# alpha85_mem_acia_pio-routed.net
KiCad netlist of a schematic drawn in EAGLE
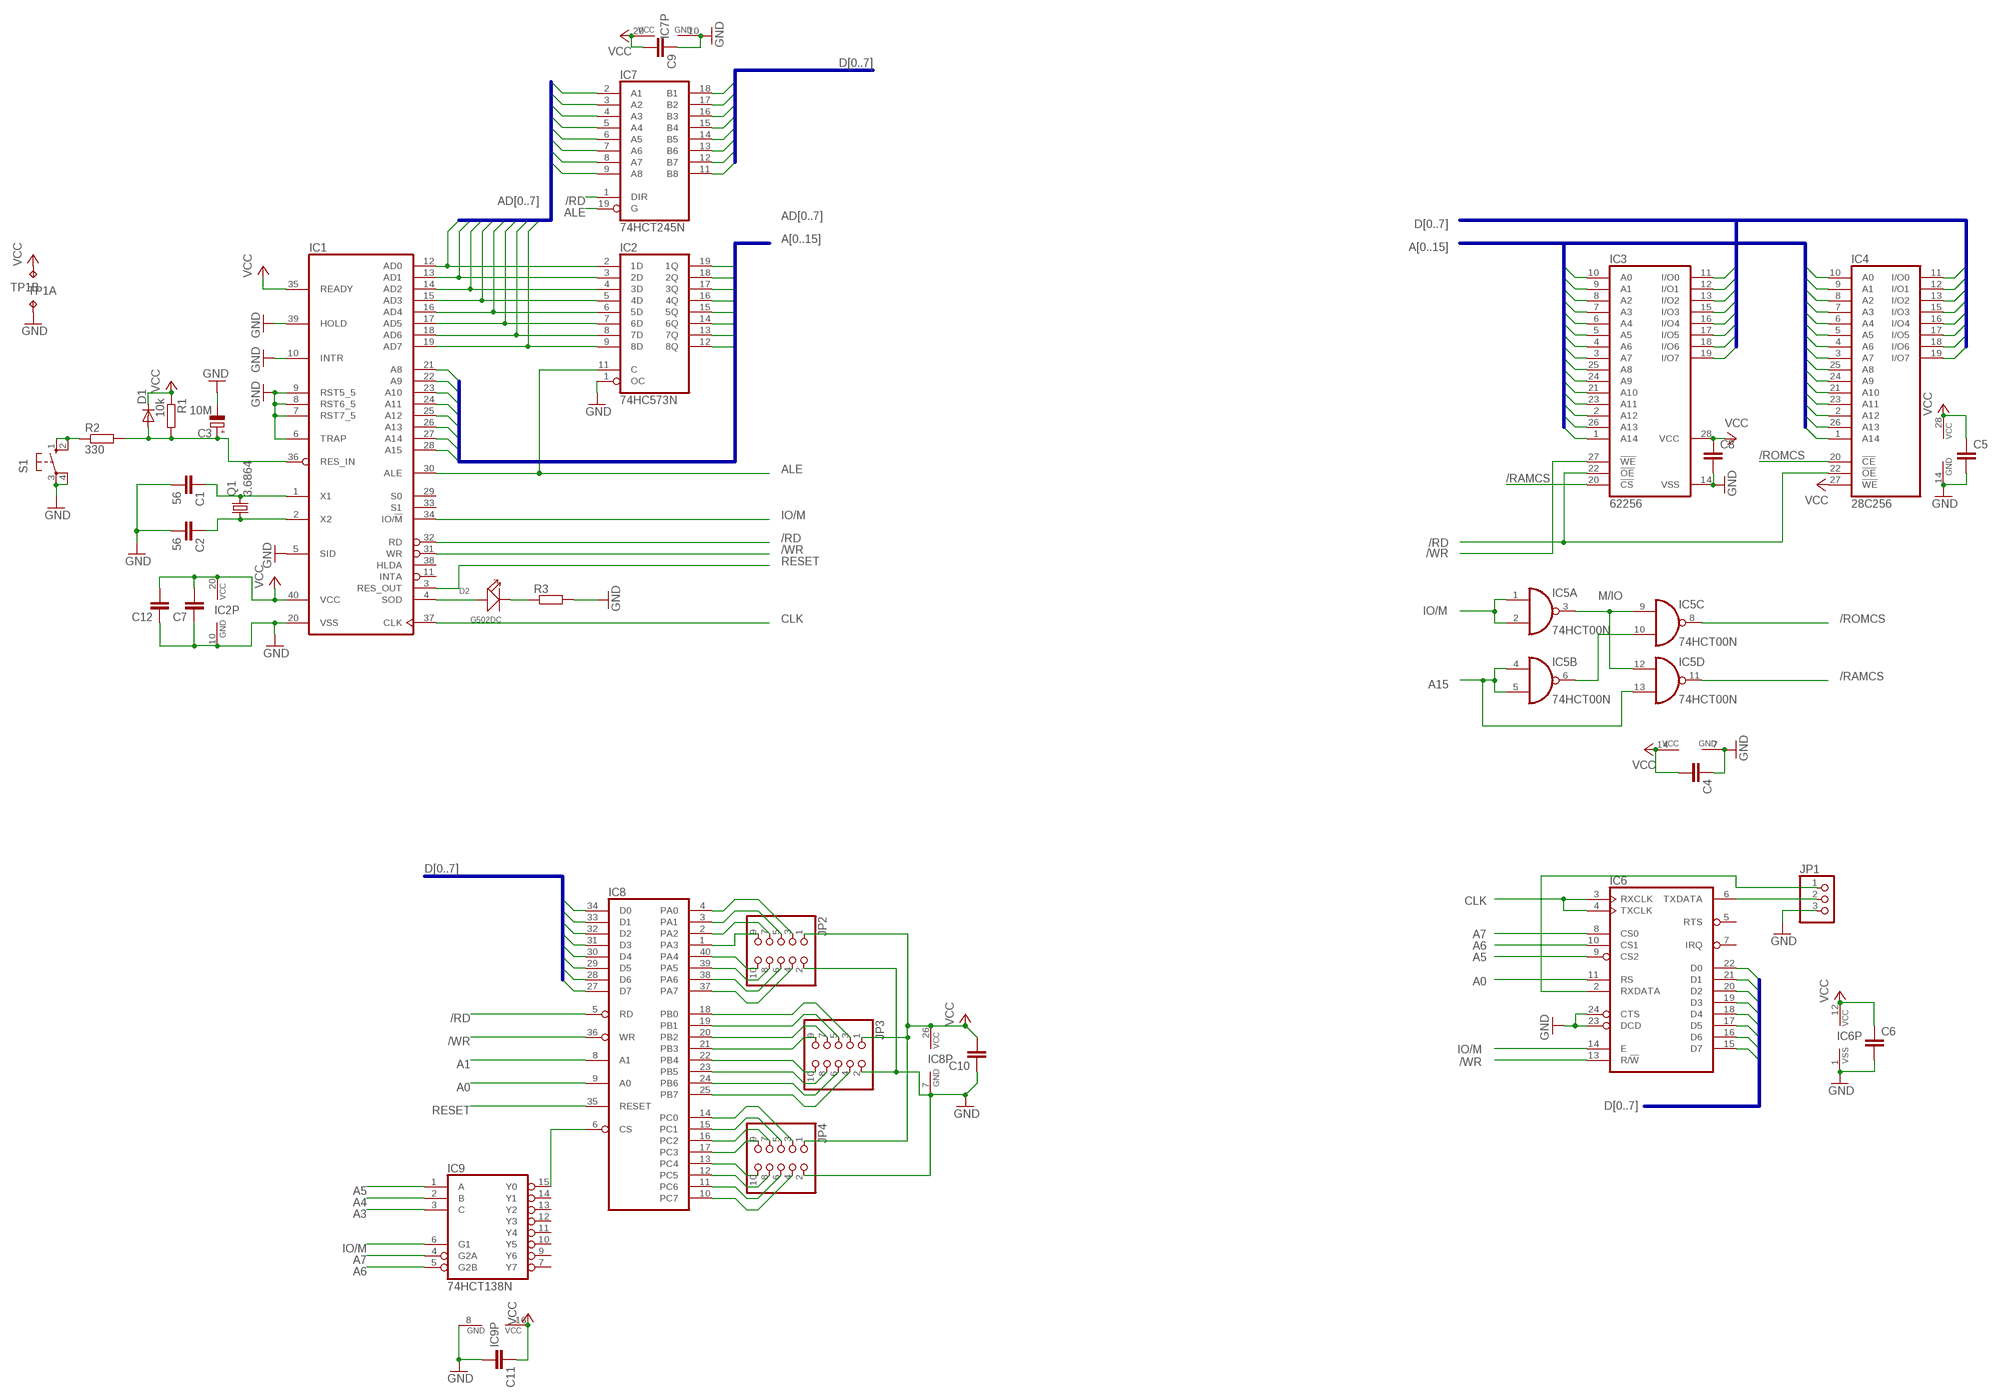
[diagram p0: schematic, sheet 1]

(export (version "E")
  (design (tool "Eeschema 10.0.6"))
  (components
    (comp (ref "C1")
      (value "56")
      (footprint "eagle-import:C025-040X050")
      (libsource (lib "eagle-import") (part "C-EU025-040X050"))
    )
    (comp (ref "C2")
      (value "56")
      (footprint "eagle-import:C025-040X050")
      (libsource (lib "eagle-import") (part "C-EU025-040X050"))
    )
    (comp (ref "C3")
      (value "10M")
      (footprint "eagle-import:E5-8,5")
      (libsource (lib "eagle-import") (part "CPOL-EUE5-8.5"))
    )
    (comp (ref "C4")
      (value "C-EU050-025X075")
      (footprint "eagle-import:C050-025X075")
      (libsource (lib "eagle-import") (part "C-EU050-025X075"))
    )
    (comp (ref "C5")
      (value "C-EU050-025X075")
      (footprint "eagle-import:C050-025X075")
      (libsource (lib "eagle-import") (part "C-EU050-025X075"))
    )
    (comp (ref "C6")
      (value "C-EU050-025X075")
      (footprint "eagle-import:C050-025X075")
      (libsource (lib "eagle-import") (part "C-EU050-025X075"))
    )
    (comp (ref "C7")
      (value "C-EU050-025X075")
      (footprint "eagle-import:C050-025X075")
      (libsource (lib "eagle-import") (part "C-EU050-025X075"))
    )
    (comp (ref "C8")
      (value "C-EU050-025X075")
      (footprint "eagle-import:C050-025X075")
      (libsource (lib "eagle-import") (part "C-EU050-025X075"))
    )
    (comp (ref "C9")
      (value "C-EU050-025X075")
      (footprint "eagle-import:C050-025X075")
      (libsource (lib "eagle-import") (part "C-EU050-025X075"))
    )
    (comp (ref "C10")
      (value "C-EU050-025X075")
      (footprint "eagle-import:C050-025X075")
      (libsource (lib "eagle-import") (part "C-EU050-025X075"))
    )
    (comp (ref "C11")
      (value "C-EU050-025X075")
      (footprint "eagle-import:C050-025X075")
      (libsource (lib "eagle-import") (part "C-EU050-025X075"))
    )
    (comp (ref "C12")
      (value "C-EU050-025X075")
      (footprint "eagle-import:C050-025X075")
      (libsource (lib "eagle-import") (part "C-EU050-025X075"))
    )
    (comp (ref "D1")
      (value "1N4004")
      (footprint "eagle-import:DO41-10")
      (libsource (lib "eagle-import") (part "1N4004"))
    )
    (comp (ref "D2")
      (value "G502DC")
      (footprint "eagle-import:LED2-2.54-D5.0MM")
      (libsource (lib "eagle-import") (part "DIP-LED-GREEN-GREEN(2P-D5MM)"))
    )
    (comp (ref "IC1")
      (value "8085")
      (footprint "eagle-import:DIL40")
      (libsource (lib "eagle-import") (part "8085"))
    )
    (comp (ref "IC2")
      (value "74HC573N")
      (footprint "eagle-import:DIL20")
      (libsource (lib "eagle-import") (part "74573NHC"))
    )
    (comp (ref "IC3")
      (value "62256")
      (footprint "eagle-import:DIL28-6")
      (libsource (lib "eagle-import") (part "62256P"))
    )
    (comp (ref "IC4")
      (value "28C256")
      (footprint "eagle-import:DIL28")
      (libsource (lib "eagle-import") (part "28C256"))
    )
    (comp (ref "IC5")
      (value "74HCT00N")
      (footprint "eagle-import:DIL14")
      (libsource (lib "eagle-import") (part "7400NHCT"))
    )
    (comp (ref "IC6")
      (value "6850")
      (footprint "eagle-import:DIL24")
      (fields (field (name "MF") "NTE ELECTRONICS") (field (name "MPN") "NTE6850"))
      (libsource (lib "eagle-import") (part "6850"))
    )
    (comp (ref "IC7")
      (value "74HCT245N")
      (footprint "eagle-import:DIL20")
      (libsource (lib "eagle-import") (part "74245NHCT"))
    )
    (comp (ref "IC8")
      (value "8255A")
      (footprint "eagle-import:DIL40")
      (libsource (lib "eagle-import") (part "8255A"))
    )
    (comp (ref "IC9")
      (value "74HCT138N")
      (footprint "eagle-import:DIL16")
      (libsource (lib "eagle-import") (part "74138NHCT"))
    )
    (comp (ref "JP1")
      (value "PINHD-1X3")
      (footprint "eagle-import:1X03")
      (libsource (lib "eagle-import") (part "PINHD-1X3"))
    )
    (comp (ref "JP2")
      (value "PINHD-2X5")
      (footprint "eagle-import:2X05")
      (libsource (lib "eagle-import") (part "PINHD-2X5"))
    )
    (comp (ref "JP3")
      (value "PINHD-2X5")
      (footprint "eagle-import:2X05")
      (libsource (lib "eagle-import") (part "PINHD-2X5"))
    )
    (comp (ref "JP4")
      (value "PINHD-2X5")
      (footprint "eagle-import:2X05")
      (libsource (lib "eagle-import") (part "PINHD-2X5"))
    )
    (comp (ref "Q1")
      (value "3.6864")
      (footprint "eagle-import:HC49_S")
      (libsource (lib "eagle-import") (part "CRYSTALHC49S"))
    )
    (comp (ref "R1")
      (value "10k")
      (footprint "eagle-import:0207_10")
      (libsource (lib "eagle-import") (part "R-EU_0207/10"))
    )
    (comp (ref "R2")
      (value "330")
      (footprint "eagle-import:0207_10")
      (libsource (lib "eagle-import") (part "R-EU_0207/10"))
    )
    (comp (ref "R3")
      (value "R-EU_0207/7")
      (footprint "eagle-import:0207_7")
      (libsource (lib "eagle-import") (part "R-EU_0207/7"))
    )
    (comp (ref "S1")
      (value "40-XX")
      (footprint "eagle-import:B3F-40XX")
      (fields (field (name "MF") "OMRON COMPONENTS USA") (field (name "MPN") "B3F-4000"))
      (libsource (lib "eagle-import") (part "40-XX"))
    )
    (comp (ref "TP1")
      (value "TP2P2-38-17")
      (footprint "eagle-import:P2-38-17")
      (libsource (lib "eagle-import") (part "TP2P2-38-17"))
    )
  )
  (nets
    (net (code "9") (name "/A0") (class "Default")
      (node (ref "IC2") (pin "19") (pinfunction "1Q_19") (pintype "tri_state"))
      (node (ref "IC3") (pin "10") (pinfunction "A0_10") (pintype "input"))
      (node (ref "IC4") (pin "10") (pinfunction "A0_10") (pintype "input"))
      (node (ref "IC6") (pin "11") (pinfunction "RS_11") (pintype "input"))
      (node (ref "IC8") (pin "9") (pinfunction "A0_9") (pintype "input"))
    )
    (net (code "10") (name "/A1") (class "Default")
      (node (ref "IC2") (pin "18") (pinfunction "2Q_18") (pintype "tri_state"))
      (node (ref "IC3") (pin "9") (pinfunction "A1_9") (pintype "input"))
      (node (ref "IC4") (pin "9") (pinfunction "A1_9") (pintype "input"))
      (node (ref "IC8") (pin "8") (pinfunction "A1_8") (pintype "input"))
    )
    (net (code "11") (name "/A2") (class "Default")
      (node (ref "IC2") (pin "17") (pinfunction "3Q_17") (pintype "tri_state"))
      (node (ref "IC3") (pin "8") (pinfunction "A2_8") (pintype "input"))
      (node (ref "IC4") (pin "8") (pinfunction "A2_8") (pintype "input"))
    )
    (net (code "12") (name "/A3") (class "Default")
      (node (ref "IC2") (pin "16") (pinfunction "4Q_16") (pintype "tri_state"))
      (node (ref "IC3") (pin "7") (pinfunction "A3_7") (pintype "input"))
      (node (ref "IC4") (pin "7") (pinfunction "A3_7") (pintype "input"))
      (node (ref "IC9") (pin "3") (pinfunction "C_3") (pintype "input"))
    )
    (net (code "13") (name "/A4") (class "Default")
      (node (ref "IC2") (pin "15") (pinfunction "5Q_15") (pintype "tri_state"))
      (node (ref "IC3") (pin "6") (pinfunction "A4_6") (pintype "input"))
      (node (ref "IC4") (pin "6") (pinfunction "A4_6") (pintype "input"))
      (node (ref "IC9") (pin "2") (pinfunction "B_2") (pintype "input"))
    )
    (net (code "14") (name "/A5") (class "Default")
      (node (ref "IC2") (pin "14") (pinfunction "6Q_14") (pintype "tri_state"))
      (node (ref "IC3") (pin "5") (pinfunction "A5_5") (pintype "input"))
      (node (ref "IC4") (pin "5") (pinfunction "A5_5") (pintype "input"))
      (node (ref "IC6") (pin "9") (pinfunction "CS2_9") (pintype "input"))
      (node (ref "IC9") (pin "1") (pinfunction "A_1") (pintype "input"))
    )
    (net (code "15") (name "/A6") (class "Default")
      (node (ref "IC2") (pin "13") (pinfunction "7Q_13") (pintype "tri_state"))
      (node (ref "IC3") (pin "4") (pinfunction "A6_4") (pintype "input"))
      (node (ref "IC4") (pin "4") (pinfunction "A6_4") (pintype "input"))
      (node (ref "IC6") (pin "10") (pinfunction "CS1_10") (pintype "input"))
      (node (ref "IC9") (pin "5") (pinfunction "G2B_5") (pintype "input"))
    )
    (net (code "16") (name "/A7") (class "Default")
      (node (ref "IC2") (pin "12") (pinfunction "8Q_12") (pintype "tri_state"))
      (node (ref "IC3") (pin "3") (pinfunction "A7_3") (pintype "input"))
      (node (ref "IC4") (pin "3") (pinfunction "A7_3") (pintype "input"))
      (node (ref "IC6") (pin "8") (pinfunction "CS0_8") (pintype "input"))
      (node (ref "IC9") (pin "4") (pinfunction "G2A_4") (pintype "input"))
    )
    (net (code "17") (name "/A8") (class "Default")
      (node (ref "IC1") (pin "21") (pinfunction "A8_21") (pintype "output"))
      (node (ref "IC3") (pin "25") (pinfunction "A8_25") (pintype "input"))
      (node (ref "IC4") (pin "25") (pinfunction "A8_25") (pintype "input"))
    )
    (net (code "18") (name "/A9") (class "Default")
      (node (ref "IC1") (pin "22") (pinfunction "A9_22") (pintype "output"))
      (node (ref "IC3") (pin "24") (pinfunction "A9_24") (pintype "input"))
      (node (ref "IC4") (pin "24") (pinfunction "A9_24") (pintype "input"))
    )
    (net (code "19") (name "/A10") (class "Default")
      (node (ref "IC1") (pin "23") (pinfunction "A10_23") (pintype "output"))
      (node (ref "IC3") (pin "21") (pinfunction "A10_21") (pintype "input"))
      (node (ref "IC4") (pin "21") (pinfunction "A10_21") (pintype "input"))
    )
    (net (code "20") (name "/A11") (class "Default")
      (node (ref "IC1") (pin "24") (pinfunction "A11_24") (pintype "output"))
      (node (ref "IC3") (pin "23") (pinfunction "A11_23") (pintype "input"))
      (node (ref "IC4") (pin "23") (pinfunction "A11_23") (pintype "input"))
    )
    (net (code "21") (name "/A12") (class "Default")
      (node (ref "IC1") (pin "25") (pinfunction "A12_25") (pintype "output"))
      (node (ref "IC3") (pin "2") (pinfunction "A12_2") (pintype "input"))
      (node (ref "IC4") (pin "2") (pinfunction "A12_2") (pintype "input"))
    )
    (net (code "22") (name "/A13") (class "Default")
      (node (ref "IC1") (pin "26") (pinfunction "A13_26") (pintype "output"))
      (node (ref "IC3") (pin "26") (pinfunction "A13_26") (pintype "input"))
      (node (ref "IC4") (pin "26") (pinfunction "A13_26") (pintype "input"))
    )
    (net (code "23") (name "/A14") (class "Default")
      (node (ref "IC1") (pin "27") (pinfunction "A14_27") (pintype "output"))
      (node (ref "IC3") (pin "1") (pinfunction "A14_1") (pintype "input"))
      (node (ref "IC4") (pin "1") (pinfunction "A14_1") (pintype "input"))
    )
    (net (code "24") (name "/A15") (class "Default")
      (node (ref "IC1") (pin "28") (pinfunction "A15_28") (pintype "output"))
      (node (ref "IC5") (pin "13") (pinfunction "I1_13") (pintype "input"))
      (node (ref "IC5") (pin "4") (pinfunction "I0_4") (pintype "input"))
      (node (ref "IC5") (pin "5") (pinfunction "I1_5") (pintype "input"))
    )
    (net (code "26") (name "/ALE") (class "Default")
      (node (ref "IC1") (pin "30") (pinfunction "ALE_30") (pintype "output"))
      (node (ref "IC2") (pin "11") (pinfunction "C_11") (pintype "input"))
      (node (ref "IC7") (pin "19") (pinfunction "G_19") (pintype "input"))
    )
    (net (code "28") (name "/CLK") (class "Default")
      (node (ref "IC1") (pin "37") (pinfunction "CLK_37") (pintype "output"))
      (node (ref "IC6") (pin "3") (pinfunction "RXCLK_3") (pintype "input"))
      (node (ref "IC6") (pin "4") (pinfunction "TXCLK_4") (pintype "input"))
    )
    (net (code "29") (name "/D0") (class "Default")
      (node (ref "IC3") (pin "11") (pinfunction "I/O0_11") (pintype "bidirectional"))
      (node (ref "IC4") (pin "11") (pinfunction "I/O0_11") (pintype "tri_state"))
      (node (ref "IC6") (pin "22") (pinfunction "D0_22") (pintype "bidirectional"))
      (node (ref "IC7") (pin "18") (pinfunction "B1_18") (pintype "bidirectional"))
      (node (ref "IC8") (pin "34") (pinfunction "D0_34") (pintype "bidirectional"))
    )
    (net (code "30") (name "/D1") (class "Default")
      (node (ref "IC3") (pin "12") (pinfunction "I/O1_12") (pintype "bidirectional"))
      (node (ref "IC4") (pin "12") (pinfunction "I/O1_12") (pintype "tri_state"))
      (node (ref "IC6") (pin "21") (pinfunction "D1_21") (pintype "bidirectional"))
      (node (ref "IC7") (pin "17") (pinfunction "B2_17") (pintype "bidirectional"))
      (node (ref "IC8") (pin "33") (pinfunction "D1_33") (pintype "bidirectional"))
    )
    (net (code "31") (name "/D2") (class "Default")
      (node (ref "IC3") (pin "13") (pinfunction "I/O2_13") (pintype "bidirectional"))
      (node (ref "IC4") (pin "13") (pinfunction "I/O2_13") (pintype "tri_state"))
      (node (ref "IC6") (pin "20") (pinfunction "D2_20") (pintype "bidirectional"))
      (node (ref "IC7") (pin "16") (pinfunction "B3_16") (pintype "bidirectional"))
      (node (ref "IC8") (pin "32") (pinfunction "D2_32") (pintype "bidirectional"))
    )
    (net (code "32") (name "/D3") (class "Default")
      (node (ref "IC3") (pin "15") (pinfunction "I/O3_15") (pintype "bidirectional"))
      (node (ref "IC4") (pin "15") (pinfunction "I/O3_15") (pintype "tri_state"))
      (node (ref "IC6") (pin "19") (pinfunction "D3_19") (pintype "bidirectional"))
      (node (ref "IC7") (pin "15") (pinfunction "B4_15") (pintype "bidirectional"))
      (node (ref "IC8") (pin "31") (pinfunction "D3_31") (pintype "bidirectional"))
    )
    (net (code "33") (name "/D4") (class "Default")
      (node (ref "IC3") (pin "16") (pinfunction "I/O4_16") (pintype "bidirectional"))
      (node (ref "IC4") (pin "16") (pinfunction "I/O4_16") (pintype "tri_state"))
      (node (ref "IC6") (pin "18") (pinfunction "D4_18") (pintype "bidirectional"))
      (node (ref "IC7") (pin "14") (pinfunction "B5_14") (pintype "bidirectional"))
      (node (ref "IC8") (pin "30") (pinfunction "D4_30") (pintype "bidirectional"))
    )
    (net (code "34") (name "/D5") (class "Default")
      (node (ref "IC3") (pin "17") (pinfunction "I/O5_17") (pintype "bidirectional"))
      (node (ref "IC4") (pin "17") (pinfunction "I/O5_17") (pintype "tri_state"))
      (node (ref "IC6") (pin "17") (pinfunction "D5_17") (pintype "bidirectional"))
      (node (ref "IC7") (pin "13") (pinfunction "B6_13") (pintype "bidirectional"))
      (node (ref "IC8") (pin "29") (pinfunction "D5_29") (pintype "bidirectional"))
    )
    (net (code "35") (name "/D6") (class "Default")
      (node (ref "IC3") (pin "18") (pinfunction "I/O6_18") (pintype "bidirectional"))
      (node (ref "IC4") (pin "18") (pinfunction "I/O6_18") (pintype "tri_state"))
      (node (ref "IC6") (pin "16") (pinfunction "D6_16") (pintype "bidirectional"))
      (node (ref "IC7") (pin "12") (pinfunction "B7_12") (pintype "bidirectional"))
      (node (ref "IC8") (pin "28") (pinfunction "D6_28") (pintype "bidirectional"))
    )
    (net (code "36") (name "/D7") (class "Default")
      (node (ref "IC3") (pin "19") (pinfunction "I/O7_19") (pintype "bidirectional"))
      (node (ref "IC4") (pin "19") (pinfunction "I/O7_19") (pintype "tri_state"))
      (node (ref "IC6") (pin "15") (pinfunction "D7_15") (pintype "bidirectional"))
      (node (ref "IC7") (pin "11") (pinfunction "B8_11") (pintype "bidirectional"))
      (node (ref "IC8") (pin "27") (pinfunction "D7_27") (pintype "bidirectional"))
    )
    (net (code "37") (name "/DX0") (class "Default")
      (node (ref "IC1") (pin "12") (pinfunction "AD0_12") (pintype "bidirectional"))
      (node (ref "IC2") (pin "2") (pinfunction "1D_2") (pintype "input"))
      (node (ref "IC7") (pin "2") (pinfunction "A1_2") (pintype "bidirectional"))
    )
    (net (code "38") (name "/DX1") (class "Default")
      (node (ref "IC1") (pin "13") (pinfunction "AD1_13") (pintype "bidirectional"))
      (node (ref "IC2") (pin "3") (pinfunction "2D_3") (pintype "input"))
      (node (ref "IC7") (pin "3") (pinfunction "A2_3") (pintype "bidirectional"))
    )
    (net (code "39") (name "/DX2") (class "Default")
      (node (ref "IC1") (pin "14") (pinfunction "AD2_14") (pintype "bidirectional"))
      (node (ref "IC2") (pin "4") (pinfunction "3D_4") (pintype "input"))
      (node (ref "IC7") (pin "4") (pinfunction "A3_4") (pintype "bidirectional"))
    )
    (net (code "40") (name "/DX3") (class "Default")
      (node (ref "IC1") (pin "15") (pinfunction "AD3_15") (pintype "bidirectional"))
      (node (ref "IC2") (pin "5") (pinfunction "4D_5") (pintype "input"))
      (node (ref "IC7") (pin "5") (pinfunction "A4_5") (pintype "bidirectional"))
    )
    (net (code "41") (name "/DX4") (class "Default")
      (node (ref "IC1") (pin "16") (pinfunction "AD4_16") (pintype "bidirectional"))
      (node (ref "IC2") (pin "6") (pinfunction "5D_6") (pintype "input"))
      (node (ref "IC7") (pin "6") (pinfunction "A5_6") (pintype "bidirectional"))
    )
    (net (code "42") (name "/DX5") (class "Default")
      (node (ref "IC1") (pin "17") (pinfunction "AD5_17") (pintype "bidirectional"))
      (node (ref "IC2") (pin "7") (pinfunction "6D_7") (pintype "input"))
      (node (ref "IC7") (pin "7") (pinfunction "A6_7") (pintype "bidirectional"))
    )
    (net (code "43") (name "/DX6") (class "Default")
      (node (ref "IC1") (pin "18") (pinfunction "AD6_18") (pintype "bidirectional"))
      (node (ref "IC2") (pin "8") (pinfunction "7D_8") (pintype "input"))
      (node (ref "IC7") (pin "8") (pinfunction "A7_8") (pintype "bidirectional"))
    )
    (net (code "44") (name "/DX7") (class "Default")
      (node (ref "IC1") (pin "19") (pinfunction "AD7_19") (pintype "bidirectional"))
      (node (ref "IC2") (pin "9") (pinfunction "8D_9") (pintype "input"))
      (node (ref "IC7") (pin "9") (pinfunction "A8_9") (pintype "bidirectional"))
    )
    (net (code "46") (name "/IO{slash}M") (class "Default")
      (node (ref "IC1") (pin "34") (pinfunction "IO/~{M}_34") (pintype "output"))
      (node (ref "IC5") (pin "1") (pinfunction "I0_1") (pintype "input"))
      (node (ref "IC5") (pin "2") (pinfunction "I1_2") (pintype "input"))
      (node (ref "IC6") (pin "14") (pinfunction "E_14") (pintype "input"))
      (node (ref "IC9") (pin "6") (pinfunction "G1_6") (pintype "input"))
    )
    (net (code "47") (name "/M{slash}IO") (class "Default")
      (node (ref "IC5") (pin "12") (pinfunction "I0_12") (pintype "input"))
      (node (ref "IC5") (pin "3") (pinfunction "O_3") (pintype "output"))
      (node (ref "IC5") (pin "9") (pinfunction "I0_9") (pintype "input"))
    )
    (net (code "48") (name "/RESET") (class "Default")
      (node (ref "IC1") (pin "3") (pinfunction "RES_OUT_3") (pintype "output"))
      (node (ref "IC8") (pin "35") (pinfunction "RESET_35") (pintype "input"))
    )
    (net (code "49") (name "/{slash}RAMCS") (class "Default")
      (node (ref "IC3") (pin "20") (pinfunction "~{CS}_20") (pintype "input"))
      (node (ref "IC5") (pin "11") (pinfunction "O_11") (pintype "output"))
    )
    (net (code "50") (name "/{slash}RD") (class "Default")
      (node (ref "IC1") (pin "32") (pinfunction "RD_32") (pintype "output"))
      (node (ref "IC3") (pin "22") (pinfunction "~{OE}_22") (pintype "input"))
      (node (ref "IC4") (pin "22") (pinfunction "~{OE}_22") (pintype "input"))
      (node (ref "IC7") (pin "1") (pinfunction "DIR_1") (pintype "input"))
      (node (ref "IC8") (pin "5") (pinfunction "RD_5") (pintype "input"))
    )
    (net (code "51") (name "/{slash}ROMCS") (class "Default")
      (node (ref "IC4") (pin "20") (pinfunction "~{CE}_20") (pintype "input"))
      (node (ref "IC5") (pin "8") (pinfunction "O_8") (pintype "output"))
    )
    (net (code "52") (name "/{slash}WR") (class "Default")
      (node (ref "IC1") (pin "31") (pinfunction "WR_31") (pintype "output"))
      (node (ref "IC3") (pin "27") (pinfunction "~{WE}_27") (pintype "input"))
      (node (ref "IC6") (pin "13") (pinfunction "R/~{W}_13") (pintype "input"))
      (node (ref "IC8") (pin "36") (pinfunction "WR_36") (pintype "input"))
    )
    (net (code "53") (name "GND") (class "Default")
      (node (ref "C1") (pin "2") (pinfunction "2_2") (pintype "passive"))
      (node (ref "C10") (pin "1") (pinfunction "1_1") (pintype "passive"))
      (node (ref "C11") (pin "2") (pinfunction "2_2") (pintype "passive"))
      (node (ref "C12") (pin "1") (pinfunction "1_1") (pintype "passive"))
      (node (ref "C2") (pin "2") (pinfunction "2_2") (pintype "passive"))
      (node (ref "C3") (pin "-") (pinfunction "-_-") (pintype "passive"))
      (node (ref "C4") (pin "1") (pinfunction "1_1") (pintype "passive"))
      (node (ref "C5") (pin "2") (pinfunction "2_2") (pintype "passive"))
      (node (ref "C6") (pin "2") (pinfunction "2_2") (pintype "passive"))
      (node (ref "C7") (pin "1") (pinfunction "1_1") (pintype "passive"))
      (node (ref "C8") (pin "2") (pinfunction "2_2") (pintype "passive"))
      (node (ref "C9") (pin "1") (pinfunction "1_1") (pintype "passive"))
      (node (ref "IC1") (pin "10") (pinfunction "INTR_10") (pintype "input"))
      (node (ref "IC1") (pin "20") (pinfunction "VSS_20") (pintype "power_in"))
      (node (ref "IC1") (pin "39") (pinfunction "HOLD_39") (pintype "input"))
      (node (ref "IC1") (pin "5") (pinfunction "SID_5") (pintype "input"))
      (node (ref "IC1") (pin "6") (pinfunction "TRAP_6") (pintype "input"))
      (node (ref "IC1") (pin "7") (pinfunction "RST7_5_7") (pintype "input"))
      (node (ref "IC1") (pin "8") (pinfunction "RST6_5_8") (pintype "input"))
      (node (ref "IC1") (pin "9") (pinfunction "RST5_5_9") (pintype "input"))
      (node (ref "IC2") (pin "1") (pinfunction "OC_1") (pintype "input"))
      (node (ref "IC2") (pin "10") (pinfunction "GND_10") (pintype "power_in"))
      (node (ref "IC3") (pin "14") (pinfunction "VSS_14") (pintype "power_in"))
      (node (ref "IC4") (pin "14") (pinfunction "GND_14") (pintype "power_in"))
      (node (ref "IC5") (pin "7") (pinfunction "GND_7") (pintype "power_in"))
      (node (ref "IC6") (pin "1") (pinfunction "VSS_1") (pintype "power_in"))
      (node (ref "IC6") (pin "23") (pinfunction "DCD_23") (pintype "input"))
      (node (ref "IC6") (pin "24") (pinfunction "CTS_24") (pintype "input"))
      (node (ref "IC7") (pin "10") (pinfunction "GND_10") (pintype "power_in"))
      (node (ref "IC8") (pin "7") (pinfunction "GND_7") (pintype "power_in"))
      (node (ref "IC9") (pin "8") (pinfunction "GND_8") (pintype "power_in"))
      (node (ref "JP1") (pin "3") (pinfunction "3_3") (pintype "passive"))
      (node (ref "JP2") (pin "2") (pinfunction "2_2") (pintype "passive"))
      (node (ref "JP3") (pin "2") (pinfunction "2_2") (pintype "passive"))
      (node (ref "JP4") (pin "2") (pinfunction "2_2") (pintype "passive"))
      (node (ref "R3") (pin "2") (pinfunction "2_2") (pintype "passive"))
      (node (ref "S1") (pin "3") (pinfunction "P_3") (pintype "passive"))
      (node (ref "S1") (pin "4") (pinfunction "P1_4") (pintype "passive"))
      (node (ref "TP1") (pin "TP-1") (pinfunction "TP_TP-1") (pintype "input"))
    )
    (net (code "54") (name "Net-(D2-Pad-)") (class "Default")
      (node (ref "D2") (pin "-") (pinfunction "-_-") (pintype "passive"))
      (node (ref "R3") (pin "1") (pinfunction "1_1") (pintype "passive"))
    )
    (net (code "55") (name "Net-(IC1-RES_IN)") (class "Default")
      (node (ref "C3") (pin "+") (pinfunction "+_+") (pintype "passive"))
      (node (ref "D1") (pin "A") (pinfunction "A_A") (pintype "passive"))
      (node (ref "IC1") (pin "36") (pinfunction "RES_IN_36") (pintype "input"))
      (node (ref "R1") (pin "2") (pinfunction "2_2") (pintype "passive"))
      (node (ref "R2") (pin "2") (pinfunction "2_2") (pintype "passive"))
    )
    (net (code "56") (name "Net-(IC1-SOD)") (class "Default")
      (node (ref "D2") (pin "+") (pinfunction "+_+") (pintype "passive"))
      (node (ref "IC1") (pin "4") (pinfunction "SOD_4") (pintype "output"))
    )
    (net (code "57") (name "Net-(IC1-X1)") (class "Default")
      (node (ref "C1") (pin "1") (pinfunction "1_1") (pintype "passive"))
      (node (ref "IC1") (pin "1") (pinfunction "X1_1") (pintype "input"))
      (node (ref "Q1") (pin "2") (pinfunction "2_2") (pintype "passive"))
    )
    (net (code "58") (name "Net-(IC1-X2)") (class "Default")
      (node (ref "C2") (pin "1") (pinfunction "1_1") (pintype "passive"))
      (node (ref "IC1") (pin "2") (pinfunction "X2_2") (pintype "input"))
      (node (ref "Q1") (pin "1") (pinfunction "1_1") (pintype "passive"))
    )
    (net (code "59") (name "Net-(IC5B-O)") (class "Default")
      (node (ref "IC5") (pin "10") (pinfunction "I1_10") (pintype "input"))
      (node (ref "IC5") (pin "6") (pinfunction "O_6") (pintype "output"))
    )
    (net (code "60") (name "Net-(IC6A-RXDATA)") (class "Default")
      (node (ref "IC6") (pin "2") (pinfunction "RXDATA_2") (pintype "input"))
      (node (ref "JP1") (pin "1") (pinfunction "1_1") (pintype "passive"))
    )
    (net (code "61") (name "Net-(IC6A-TXDATA)") (class "Default")
      (node (ref "IC6") (pin "6") (pinfunction "TXDATA_6") (pintype "output"))
      (node (ref "JP1") (pin "2") (pinfunction "2_2") (pintype "passive"))
    )
    (net (code "62") (name "Net-(IC8A-CS)") (class "Default")
      (node (ref "IC8") (pin "6") (pinfunction "CS_6") (pintype "input"))
      (node (ref "IC9") (pin "15") (pinfunction "Y0_15") (pintype "output"))
    )
    (net (code "63") (name "Net-(IC8A-PA0)") (class "Default")
      (node (ref "IC8") (pin "4") (pinfunction "PA0_4") (pintype "bidirectional"))
      (node (ref "JP2") (pin "3") (pinfunction "3_3") (pintype "passive"))
    )
    (net (code "64") (name "Net-(IC8A-PA1)") (class "Default")
      (node (ref "IC8") (pin "3") (pinfunction "PA1_3") (pintype "bidirectional"))
      (node (ref "JP2") (pin "5") (pinfunction "5_5") (pintype "passive"))
    )
    (net (code "65") (name "Net-(IC8A-PA2)") (class "Default")
      (node (ref "IC8") (pin "2") (pinfunction "PA2_2") (pintype "bidirectional"))
      (node (ref "JP2") (pin "7") (pinfunction "7_7") (pintype "passive"))
    )
    (net (code "66") (name "Net-(IC8A-PA3)") (class "Default")
      (node (ref "IC8") (pin "1") (pinfunction "PA3_1") (pintype "bidirectional"))
      (node (ref "JP2") (pin "9") (pinfunction "9_9") (pintype "passive"))
    )
    (net (code "67") (name "Net-(IC8A-PA4)") (class "Default")
      (node (ref "IC8") (pin "40") (pinfunction "PA4_40") (pintype "bidirectional"))
      (node (ref "JP2") (pin "10") (pinfunction "10_10") (pintype "passive"))
    )
    (net (code "68") (name "Net-(IC8A-PA5)") (class "Default")
      (node (ref "IC8") (pin "39") (pinfunction "PA5_39") (pintype "bidirectional"))
      (node (ref "JP2") (pin "8") (pinfunction "8_8") (pintype "passive"))
    )
    (net (code "69") (name "Net-(IC8A-PA6)") (class "Default")
      (node (ref "IC8") (pin "38") (pinfunction "PA6_38") (pintype "bidirectional"))
      (node (ref "JP2") (pin "6") (pinfunction "6_6") (pintype "passive"))
    )
    (net (code "70") (name "Net-(IC8A-PA7)") (class "Default")
      (node (ref "IC8") (pin "37") (pinfunction "PA7_37") (pintype "bidirectional"))
      (node (ref "JP2") (pin "4") (pinfunction "4_4") (pintype "passive"))
    )
    (net (code "71") (name "Net-(IC8A-PB0)") (class "Default")
      (node (ref "IC8") (pin "18") (pinfunction "PB0_18") (pintype "bidirectional"))
      (node (ref "JP3") (pin "3") (pinfunction "3_3") (pintype "passive"))
    )
    (net (code "72") (name "Net-(IC8A-PB1)") (class "Default")
      (node (ref "IC8") (pin "19") (pinfunction "PB1_19") (pintype "bidirectional"))
      (node (ref "JP3") (pin "5") (pinfunction "5_5") (pintype "passive"))
    )
    (net (code "73") (name "Net-(IC8A-PB2)") (class "Default")
      (node (ref "IC8") (pin "20") (pinfunction "PB2_20") (pintype "bidirectional"))
      (node (ref "JP3") (pin "7") (pinfunction "7_7") (pintype "passive"))
    )
    (net (code "74") (name "Net-(IC8A-PB3)") (class "Default")
      (node (ref "IC8") (pin "21") (pinfunction "PB3_21") (pintype "bidirectional"))
      (node (ref "JP3") (pin "9") (pinfunction "9_9") (pintype "passive"))
    )
    (net (code "75") (name "Net-(IC8A-PB4)") (class "Default")
      (node (ref "IC8") (pin "22") (pinfunction "PB4_22") (pintype "bidirectional"))
      (node (ref "JP3") (pin "10") (pinfunction "10_10") (pintype "passive"))
    )
    (net (code "76") (name "Net-(IC8A-PB5)") (class "Default")
      (node (ref "IC8") (pin "23") (pinfunction "PB5_23") (pintype "bidirectional"))
      (node (ref "JP3") (pin "8") (pinfunction "8_8") (pintype "passive"))
    )
    (net (code "77") (name "Net-(IC8A-PB6)") (class "Default")
      (node (ref "IC8") (pin "24") (pinfunction "PB6_24") (pintype "bidirectional"))
      (node (ref "JP3") (pin "6") (pinfunction "6_6") (pintype "passive"))
    )
    (net (code "78") (name "Net-(IC8A-PB7)") (class "Default")
      (node (ref "IC8") (pin "25") (pinfunction "PB7_25") (pintype "bidirectional"))
      (node (ref "JP3") (pin "4") (pinfunction "4_4") (pintype "passive"))
    )
    (net (code "79") (name "Net-(IC8A-PC0)") (class "Default")
      (node (ref "IC8") (pin "14") (pinfunction "PC0_14") (pintype "bidirectional"))
      (node (ref "JP4") (pin "3") (pinfunction "3_3") (pintype "passive"))
    )
    (net (code "80") (name "Net-(IC8A-PC1)") (class "Default")
      (node (ref "IC8") (pin "15") (pinfunction "PC1_15") (pintype "bidirectional"))
      (node (ref "JP4") (pin "5") (pinfunction "5_5") (pintype "passive"))
    )
    (net (code "81") (name "Net-(IC8A-PC2)") (class "Default")
      (node (ref "IC8") (pin "16") (pinfunction "PC2_16") (pintype "bidirectional"))
      (node (ref "JP4") (pin "7") (pinfunction "7_7") (pintype "passive"))
    )
    (net (code "82") (name "Net-(IC8A-PC3)") (class "Default")
      (node (ref "IC8") (pin "17") (pinfunction "PC3_17") (pintype "bidirectional"))
      (node (ref "JP4") (pin "9") (pinfunction "9_9") (pintype "passive"))
    )
    (net (code "83") (name "Net-(IC8A-PC4)") (class "Default")
      (node (ref "IC8") (pin "13") (pinfunction "PC4_13") (pintype "bidirectional"))
      (node (ref "JP4") (pin "10") (pinfunction "10_10") (pintype "passive"))
    )
    (net (code "84") (name "Net-(IC8A-PC5)") (class "Default")
      (node (ref "IC8") (pin "12") (pinfunction "PC5_12") (pintype "bidirectional"))
      (node (ref "JP4") (pin "8") (pinfunction "8_8") (pintype "passive"))
    )
    (net (code "85") (name "Net-(IC8A-PC6)") (class "Default")
      (node (ref "IC8") (pin "11") (pinfunction "PC6_11") (pintype "bidirectional"))
      (node (ref "JP4") (pin "6") (pinfunction "6_6") (pintype "passive"))
    )
    (net (code "86") (name "Net-(IC8A-PC7)") (class "Default")
      (node (ref "IC8") (pin "10") (pinfunction "PC7_10") (pintype "bidirectional"))
      (node (ref "JP4") (pin "4") (pinfunction "4_4") (pintype "passive"))
    )
    (net (code "87") (name "Net-(S1-S)") (class "Default")
      (node (ref "R2") (pin "1") (pinfunction "1_1") (pintype "passive"))
      (node (ref "S1") (pin "1") (pinfunction "S_1") (pintype "passive"))
      (node (ref "S1") (pin "2") (pinfunction "S1_2") (pintype "passive"))
    )
    (net (code "88") (name "VCC") (class "Default")
      (node (ref "C10") (pin "2") (pinfunction "2_2") (pintype "passive"))
      (node (ref "C11") (pin "1") (pinfunction "1_1") (pintype "passive"))
      (node (ref "C12") (pin "2") (pinfunction "2_2") (pintype "passive"))
      (node (ref "C4") (pin "2") (pinfunction "2_2") (pintype "passive"))
      (node (ref "C5") (pin "1") (pinfunction "1_1") (pintype "passive"))
      (node (ref "C6") (pin "1") (pinfunction "1_1") (pintype "passive"))
      (node (ref "C7") (pin "2") (pinfunction "2_2") (pintype "passive"))
      (node (ref "C8") (pin "1") (pinfunction "1_1") (pintype "passive"))
      (node (ref "C9") (pin "2") (pinfunction "2_2") (pintype "passive"))
      (node (ref "D1") (pin "C") (pinfunction "C_C") (pintype "passive"))
      (node (ref "IC1") (pin "35") (pinfunction "READY_35") (pintype "input"))
      (node (ref "IC1") (pin "40") (pinfunction "VCC_40") (pintype "power_in"))
      (node (ref "IC2") (pin "20") (pinfunction "VCC_20") (pintype "power_in"))
      (node (ref "IC3") (pin "28") (pinfunction "VCC_28") (pintype "power_in"))
      (node (ref "IC4") (pin "27") (pinfunction "~{WE}_27") (pintype "input"))
      (node (ref "IC4") (pin "28") (pinfunction "VCC_28") (pintype "power_in"))
      (node (ref "IC5") (pin "14") (pinfunction "VCC_14") (pintype "power_in"))
      (node (ref "IC6") (pin "12") (pinfunction "VCC_12") (pintype "power_in"))
      (node (ref "IC7") (pin "20") (pinfunction "VCC_20") (pintype "power_in"))
      (node (ref "IC8") (pin "26") (pinfunction "VCC_26") (pintype "power_in"))
      (node (ref "IC9") (pin "16") (pinfunction "VCC_16") (pintype "power_in"))
      (node (ref "JP2") (pin "1") (pinfunction "1_1") (pintype "passive"))
      (node (ref "JP3") (pin "1") (pinfunction "1_1") (pintype "passive"))
      (node (ref "JP4") (pin "1") (pinfunction "1_1") (pintype "passive"))
      (node (ref "R1") (pin "1") (pinfunction "1_1") (pintype "passive"))
      (node (ref "TP1") (pin "TP-2") (pinfunction "TP_TP-2") (pintype "input"))
    )
    (net (code "89") (name "unconnected-(IC1-HLDA-Pad38)") (class "Default")
      (node (ref "IC1") (pin "38") (pinfunction "HLDA_38") (pintype "output"))
    )
    (net (code "90") (name "unconnected-(IC1-INTA-Pad11)") (class "Default")
      (node (ref "IC1") (pin "11") (pinfunction "INTA_11") (pintype "output"))
    )
    (net (code "91") (name "unconnected-(IC1-S0-Pad29)") (class "Default")
      (node (ref "IC1") (pin "29") (pinfunction "S0_29") (pintype "output"))
    )
    (net (code "92") (name "unconnected-(IC1-S1-Pad33)") (class "Default")
      (node (ref "IC1") (pin "33") (pinfunction "S1_33") (pintype "output"))
    )
    (net (code "93") (name "unconnected-(IC6A-IRQ-Pad7)") (class "Default")
      (node (ref "IC6") (pin "7") (pinfunction "IRQ_7") (pintype "output"))
    )
    (net (code "94") (name "unconnected-(IC6A-RTS-Pad5)") (class "Default")
      (node (ref "IC6") (pin "5") (pinfunction "RTS_5") (pintype "output"))
    )
    (net (code "95") (name "unconnected-(IC9A-Y1-Pad14)") (class "Default")
      (node (ref "IC9") (pin "14") (pinfunction "Y1_14") (pintype "output"))
    )
    (net (code "96") (name "unconnected-(IC9A-Y2-Pad13)") (class "Default")
      (node (ref "IC9") (pin "13") (pinfunction "Y2_13") (pintype "output"))
    )
    (net (code "97") (name "unconnected-(IC9A-Y3-Pad12)") (class "Default")
      (node (ref "IC9") (pin "12") (pinfunction "Y3_12") (pintype "output"))
    )
    (net (code "98") (name "unconnected-(IC9A-Y4-Pad11)") (class "Default")
      (node (ref "IC9") (pin "11") (pinfunction "Y4_11") (pintype "output"))
    )
    (net (code "99") (name "unconnected-(IC9A-Y5-Pad10)") (class "Default")
      (node (ref "IC9") (pin "10") (pinfunction "Y5_10") (pintype "output"))
    )
    (net (code "100") (name "unconnected-(IC9A-Y6-Pad9)") (class "Default")
      (node (ref "IC9") (pin "9") (pinfunction "Y6_9") (pintype "output"))
    )
    (net (code "101") (name "unconnected-(IC9A-Y7-Pad7)") (class "Default")
      (node (ref "IC9") (pin "7") (pinfunction "Y7_7") (pintype "output"))
    )
  )
)
